# c64-uni-cart-rev5.net
KiCad netlist of a schematic drawn in EAGLE
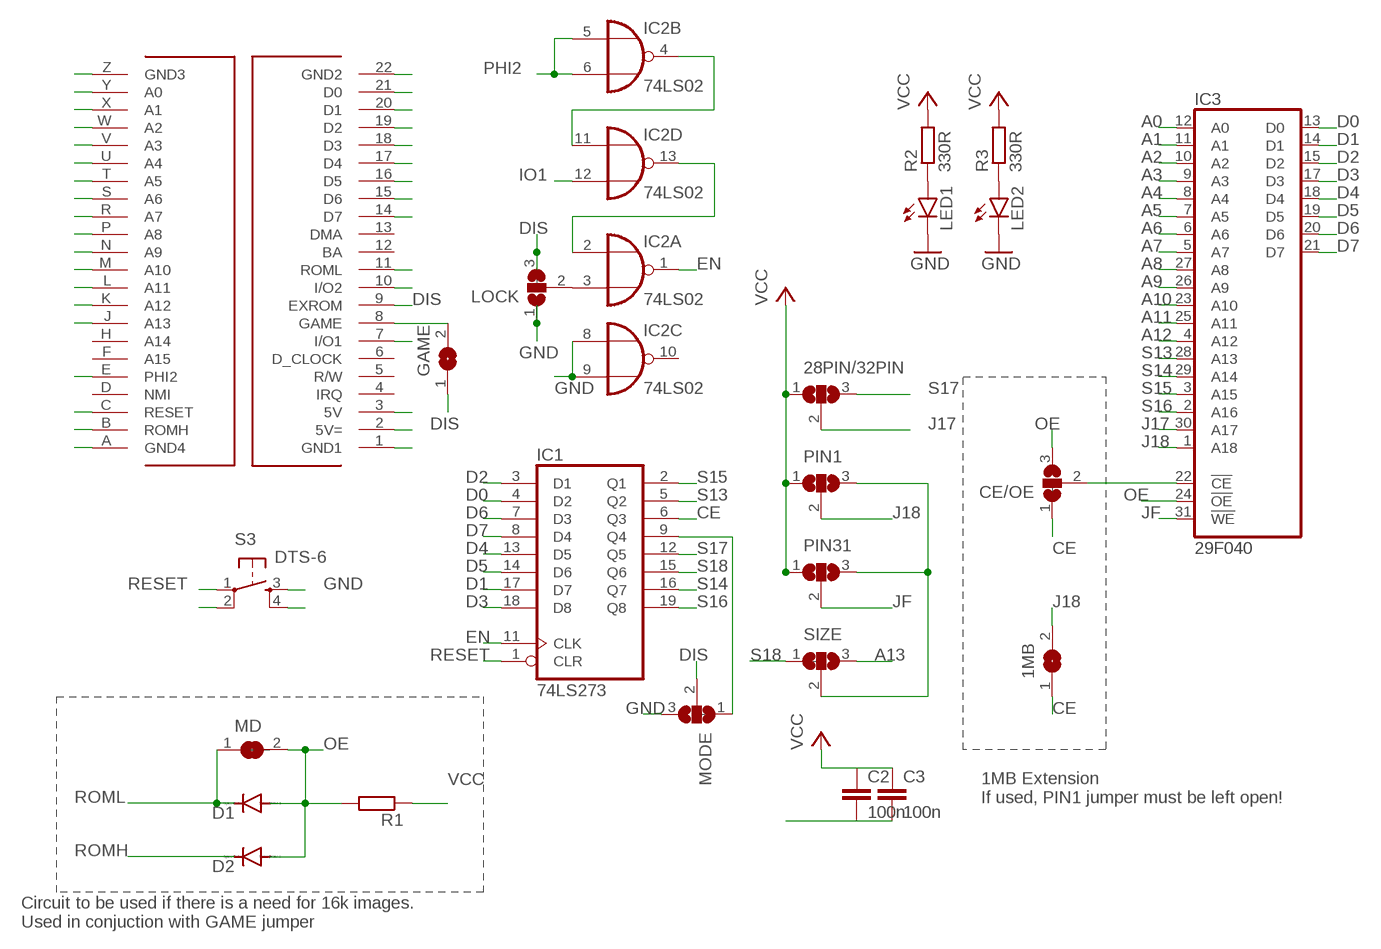
[diagram p0: schematic, sheet 1]

(export (version "E")
  (design (tool "Eeschema 10.0.6"))
  (components
    (comp (ref "1MB") (value "SJ") (footprint "eagle-import:SJ") (libsource (lib "eagle-import") (part "SJ")))
    (comp (ref "28PIN/32PIN")
      (value "SJ2W")
      (footprint "eagle-import:SJ_2")
      (libsource (lib "eagle-import") (part "SJ2W"))
    )
    (comp (ref "C2")
      (value "100n")
      (footprint "eagle-import:C025-024X044")
      (libsource (lib "eagle-import") (part "C-EU025-024X044"))
    )
    (comp (ref "C3")
      (value "100n")
      (footprint "eagle-import:C025-024X044")
      (libsource (lib "eagle-import") (part "C-EU025-024X044"))
    )
    (comp (ref "CE/OE")
      (value "SJ2W")
      (footprint "eagle-import:SJ_2")
      (libsource (lib "eagle-import") (part "SJ2W"))
    )
    (comp (ref "D1")
      (value "DIODE-MINIMELF")
      (footprint "eagle-import:MINIMELF")
      (libsource (lib "eagle-import") (part "DIODE-MINIMELF"))
    )
    (comp (ref "D2")
      (value "DIODE-MINIMELF")
      (footprint "eagle-import:MINIMELF")
      (libsource (lib "eagle-import") (part "DIODE-MINIMELF"))
    )
    (comp (ref "GAME")
      (value "SJ")
      (footprint "eagle-import:SJ")
      (libsource (lib "eagle-import") (part "SJ"))
    )
    (comp (ref "IC1")
      (value "74LS273")
      (footprint "eagle-import:DIL20")
      (libsource (lib "eagle-import") (part "74273NHCT"))
    )
    (comp (ref "IC2")
      (value "74LS02")
      (footprint "eagle-import:DIL14")
      (libsource (lib "eagle-import") (part "7402NLS"))
    )
    (comp (ref "IC3")
      (value "29F040")
      (footprint "eagle-import:DIL32-6")
      (libsource (lib "eagle-import") (part "AM29F040N"))
    )
    (comp (ref "LED1")
      (value "LED3MM")
      (footprint "eagle-import:LED3MM")
      (libsource (lib "eagle-import") (part "LED3MM"))
    )
    (comp (ref "LED2")
      (value "LED3MM")
      (footprint "eagle-import:LED3MM")
      (libsource (lib "eagle-import") (part "LED3MM"))
    )
    (comp (ref "LOCK")
      (value "SJ2W")
      (footprint "eagle-import:SJ_2")
      (libsource (lib "eagle-import") (part "SJ2W"))
    )
    (comp (ref "MD") (value "SJ") (footprint "eagle-import:SJ") (libsource (lib "eagle-import") (part "SJ")))
    (comp (ref "MODE")
      (value "SJ2W")
      (footprint "eagle-import:SJ_2")
      (libsource (lib "eagle-import") (part "SJ2W"))
    )
    (comp (ref "PIN1")
      (value "SJ2W")
      (footprint "eagle-import:SJ_2")
      (libsource (lib "eagle-import") (part "SJ2W"))
    )
    (comp (ref "PIN31")
      (value "SJ2W")
      (footprint "eagle-import:SJ_2")
      (libsource (lib "eagle-import") (part "SJ2W"))
    )
    (comp (ref "R1")
      (value "R-EU_R1206")
      (footprint "eagle-import:R1206")
      (libsource (lib "eagle-import") (part "R-EU_R1206"))
    )
    (comp (ref "R2")
      (value "330R")
      (footprint "eagle-import:R0805")
      (libsource (lib "eagle-import") (part "R-EU_R0805"))
    )
    (comp (ref "R3")
      (value "330R")
      (footprint "eagle-import:R0805")
      (libsource (lib "eagle-import") (part "R-EU_R0805"))
    )
    (comp (ref "S3")
      (value "DTS-6")
      (footprint "eagle-import:DTS-6")
      (libsource (lib "eagle-import") (part "DTS-6"))
    )
    (comp (ref "SIZE")
      (value "SJ2W")
      (footprint "eagle-import:SJ_2")
      (libsource (lib "eagle-import") (part "SJ2W"))
    )
    (comp (ref "U$1")
      (value "C64_CARTRIDGESTUMPY")
      (footprint "eagle-import:C64_STUMPY")
      (libsource (lib "eagle-import") (part "C64_CARTRIDGESTUMPY"))
    )
  )
  (nets
    (net (code "1") (name "/A0") (class "Default")
      (node (ref "IC3") (pin "12") (pinfunction "A0_12") (pintype "input"))
      (node (ref "U$1") (pin "Y") (pinfunction "A0_Y") (pintype "bidirectional"))
    )
    (net (code "2") (name "/A1") (class "Default")
      (node (ref "IC3") (pin "11") (pinfunction "A1_11") (pintype "input"))
      (node (ref "U$1") (pin "X") (pinfunction "A1_X") (pintype "bidirectional"))
    )
    (net (code "3") (name "/A2") (class "Default")
      (node (ref "IC3") (pin "10") (pinfunction "A2_10") (pintype "input"))
      (node (ref "U$1") (pin "W") (pinfunction "A2_W") (pintype "bidirectional"))
    )
    (net (code "4") (name "/A3") (class "Default")
      (node (ref "IC3") (pin "9") (pinfunction "A3_9") (pintype "input"))
      (node (ref "U$1") (pin "V") (pinfunction "A3_V") (pintype "bidirectional"))
    )
    (net (code "5") (name "/A4") (class "Default")
      (node (ref "IC3") (pin "8") (pinfunction "A4_8") (pintype "input"))
      (node (ref "U$1") (pin "U") (pinfunction "A4_U") (pintype "bidirectional"))
    )
    (net (code "6") (name "/A5") (class "Default")
      (node (ref "IC3") (pin "7") (pinfunction "A5_7") (pintype "input"))
      (node (ref "U$1") (pin "T") (pinfunction "A5_T") (pintype "bidirectional"))
    )
    (net (code "7") (name "/A6") (class "Default")
      (node (ref "IC3") (pin "6") (pinfunction "A6_6") (pintype "input"))
      (node (ref "U$1") (pin "S") (pinfunction "A6_S") (pintype "bidirectional"))
    )
    (net (code "8") (name "/A7") (class "Default")
      (node (ref "IC3") (pin "5") (pinfunction "A7_5") (pintype "input"))
      (node (ref "U$1") (pin "R") (pinfunction "A7_R") (pintype "bidirectional"))
    )
    (net (code "9") (name "/A8") (class "Default")
      (node (ref "IC3") (pin "27") (pinfunction "A8_27") (pintype "input"))
      (node (ref "U$1") (pin "P") (pinfunction "A8_P") (pintype "bidirectional"))
    )
    (net (code "10") (name "/A9") (class "Default")
      (node (ref "IC3") (pin "26") (pinfunction "A9_26") (pintype "input"))
      (node (ref "U$1") (pin "N") (pinfunction "A9_N") (pintype "bidirectional"))
    )
    (net (code "11") (name "/A10") (class "Default")
      (node (ref "IC3") (pin "23") (pinfunction "A10_23") (pintype "input"))
      (node (ref "U$1") (pin "M") (pinfunction "A10_M") (pintype "bidirectional"))
    )
    (net (code "12") (name "/A11") (class "Default")
      (node (ref "IC3") (pin "25") (pinfunction "A11_25") (pintype "input"))
      (node (ref "U$1") (pin "L") (pinfunction "A11_L") (pintype "bidirectional"))
    )
    (net (code "13") (name "/A12") (class "Default")
      (node (ref "IC3") (pin "4") (pinfunction "A12_4") (pintype "input"))
      (node (ref "U$1") (pin "K") (pinfunction "A12_K") (pintype "bidirectional"))
    )
    (net (code "14") (name "/A13") (class "Default")
      (node (ref "SIZE") (pin "3") (pinfunction "3_3") (pintype "passive"))
      (node (ref "U$1") (pin "J") (pinfunction "A13_J") (pintype "bidirectional"))
    )
    (net (code "15") (name "/CE") (class "Default")
      (node (ref "1MB") (pin "1") (pinfunction "1_1") (pintype "passive"))
      (node (ref "CE/OE") (pin "1") (pinfunction "1_1") (pintype "passive"))
      (node (ref "IC1") (pin "6") (pinfunction "Q3_6") (pintype "output"))
    )
    (net (code "16") (name "/D0") (class "Default")
      (node (ref "IC1") (pin "4") (pinfunction "D2_4") (pintype "input"))
      (node (ref "IC3") (pin "13") (pinfunction "D0_13") (pintype "tri_state"))
      (node (ref "U$1") (pin "21") (pinfunction "D0_21") (pintype "bidirectional"))
    )
    (net (code "17") (name "/D1") (class "Default")
      (node (ref "IC1") (pin "17") (pinfunction "D7_17") (pintype "input"))
      (node (ref "IC3") (pin "14") (pinfunction "D1_14") (pintype "tri_state"))
      (node (ref "U$1") (pin "20") (pinfunction "D1_20") (pintype "bidirectional"))
    )
    (net (code "18") (name "/D2") (class "Default")
      (node (ref "IC1") (pin "3") (pinfunction "D1_3") (pintype "input"))
      (node (ref "IC3") (pin "15") (pinfunction "D2_15") (pintype "tri_state"))
      (node (ref "U$1") (pin "19") (pinfunction "D2_19") (pintype "bidirectional"))
    )
    (net (code "19") (name "/D3") (class "Default")
      (node (ref "IC1") (pin "18") (pinfunction "D8_18") (pintype "input"))
      (node (ref "IC3") (pin "17") (pinfunction "D3_17") (pintype "tri_state"))
      (node (ref "U$1") (pin "18") (pinfunction "D3_18") (pintype "bidirectional"))
    )
    (net (code "20") (name "/D4") (class "Default")
      (node (ref "IC1") (pin "13") (pinfunction "D5_13") (pintype "input"))
      (node (ref "IC3") (pin "18") (pinfunction "D4_18") (pintype "tri_state"))
      (node (ref "U$1") (pin "17") (pinfunction "D4_17") (pintype "bidirectional"))
    )
    (net (code "21") (name "/D5") (class "Default")
      (node (ref "IC1") (pin "14") (pinfunction "D6_14") (pintype "input"))
      (node (ref "IC3") (pin "19") (pinfunction "D5_19") (pintype "tri_state"))
      (node (ref "U$1") (pin "16") (pinfunction "D5_16") (pintype "bidirectional"))
    )
    (net (code "22") (name "/D6") (class "Default")
      (node (ref "IC1") (pin "7") (pinfunction "D3_7") (pintype "input"))
      (node (ref "IC3") (pin "20") (pinfunction "D6_20") (pintype "tri_state"))
      (node (ref "U$1") (pin "15") (pinfunction "D6_15") (pintype "bidirectional"))
    )
    (net (code "23") (name "/D7") (class "Default")
      (node (ref "IC1") (pin "8") (pinfunction "D4_8") (pintype "input"))
      (node (ref "IC3") (pin "21") (pinfunction "D7_21") (pintype "tri_state"))
      (node (ref "U$1") (pin "14") (pinfunction "D7_14") (pintype "bidirectional"))
    )
    (net (code "24") (name "/DIS") (class "Default")
      (node (ref "GAME") (pin "1") (pinfunction "1_1") (pintype "passive"))
      (node (ref "LOCK") (pin "3") (pinfunction "3_3") (pintype "passive"))
      (node (ref "MODE") (pin "2") (pinfunction "2_2") (pintype "passive"))
      (node (ref "U$1") (pin "9") (pinfunction "EXROM_9") (pintype "bidirectional"))
    )
    (net (code "25") (name "/EN") (class "Default")
      (node (ref "IC1") (pin "11") (pinfunction "CLK_11") (pintype "input"))
      (node (ref "IC2") (pin "1") (pinfunction "O_1") (pintype "output"))
    )
    (net (code "26") (name "/IO1") (class "Default")
      (node (ref "IC2") (pin "12") (pinfunction "I1_12") (pintype "input"))
      (node (ref "U$1") (pin "7") (pinfunction "I/O1_7") (pintype "bidirectional"))
    )
    (net (code "27") (name "/J17") (class "Default")
      (node (ref "28PIN/32PIN") (pin "2") (pinfunction "2_2") (pintype "passive"))
      (node (ref "IC3") (pin "30") (pinfunction "A17_30") (pintype "input"))
    )
    (net (code "28") (name "/J18") (class "Default")
      (node (ref "1MB") (pin "2") (pinfunction "2_2") (pintype "passive"))
      (node (ref "IC3") (pin "1") (pinfunction "A18_1") (pintype "input"))
      (node (ref "PIN1") (pin "2") (pinfunction "2_2") (pintype "passive"))
    )
    (net (code "29") (name "/JF") (class "Default")
      (node (ref "IC3") (pin "31") (pinfunction "~{WE}_31") (pintype "input"))
      (node (ref "PIN31") (pin "2") (pinfunction "2_2") (pintype "passive"))
    )
    (net (code "30") (name "/OE") (class "Default")
      (node (ref "CE/OE") (pin "3") (pinfunction "3_3") (pintype "passive"))
      (node (ref "D1") (pin "A") (pinfunction "A_A") (pintype "passive"))
      (node (ref "D2") (pin "A") (pinfunction "A_A") (pintype "passive"))
      (node (ref "IC3") (pin "24") (pinfunction "~{OE}_24") (pintype "input"))
      (node (ref "MD") (pin "2") (pinfunction "2_2") (pintype "passive"))
      (node (ref "R1") (pin "2") (pinfunction "2_2") (pintype "passive"))
    )
    (net (code "31") (name "/PHI2") (class "Default")
      (node (ref "IC2") (pin "5") (pinfunction "I0_5") (pintype "input"))
      (node (ref "IC2") (pin "6") (pinfunction "I1_6") (pintype "input"))
      (node (ref "U$1") (pin "E") (pinfunction "PHI2_E") (pintype "bidirectional"))
    )
    (net (code "32") (name "/RESET") (class "Default")
      (node (ref "IC1") (pin "1") (pinfunction "CLR_1") (pintype "input"))
      (node (ref "S3") (pin "1") (pinfunction "1_1") (pintype "passive"))
      (node (ref "S3") (pin "2") (pinfunction "2_2") (pintype "passive"))
      (node (ref "U$1") (pin "C") (pinfunction "RESET_C") (pintype "bidirectional"))
    )
    (net (code "33") (name "/ROMH") (class "Default")
      (node (ref "D2") (pin "C") (pinfunction "C_C") (pintype "passive"))
      (node (ref "U$1") (pin "B") (pinfunction "ROMH_B") (pintype "bidirectional"))
    )
    (net (code "34") (name "/ROML") (class "Default")
      (node (ref "D1") (pin "C") (pinfunction "C_C") (pintype "passive"))
      (node (ref "MD") (pin "1") (pinfunction "1_1") (pintype "passive"))
      (node (ref "U$1") (pin "11") (pinfunction "ROML_11") (pintype "bidirectional"))
    )
    (net (code "35") (name "/S13") (class "Default")
      (node (ref "IC1") (pin "5") (pinfunction "Q2_5") (pintype "output"))
      (node (ref "IC3") (pin "28") (pinfunction "A13_28") (pintype "input"))
    )
    (net (code "36") (name "/S14") (class "Default")
      (node (ref "IC1") (pin "16") (pinfunction "Q7_16") (pintype "output"))
      (node (ref "IC3") (pin "29") (pinfunction "A14_29") (pintype "input"))
    )
    (net (code "37") (name "/S15") (class "Default")
      (node (ref "IC1") (pin "2") (pinfunction "Q1_2") (pintype "output"))
      (node (ref "IC3") (pin "3") (pinfunction "A15_3") (pintype "input"))
    )
    (net (code "38") (name "/S16") (class "Default")
      (node (ref "IC1") (pin "19") (pinfunction "Q8_19") (pintype "output"))
      (node (ref "IC3") (pin "2") (pinfunction "A16_2") (pintype "input"))
    )
    (net (code "39") (name "/S17") (class "Default")
      (node (ref "28PIN/32PIN") (pin "3") (pinfunction "3_3") (pintype "passive"))
      (node (ref "IC1") (pin "12") (pinfunction "Q5_12") (pintype "output"))
    )
    (net (code "40") (name "/S18") (class "Default")
      (node (ref "IC1") (pin "15") (pinfunction "Q6_15") (pintype "output"))
      (node (ref "SIZE") (pin "1") (pinfunction "1_1") (pintype "passive"))
    )
    (net (code "41") (name "GND") (class "Default")
      (node (ref "C2") (pin "2") (pinfunction "2_2") (pintype "passive"))
      (node (ref "C3") (pin "2") (pinfunction "2_2") (pintype "passive"))
      (node (ref "IC2") (pin "8") (pinfunction "I0_8") (pintype "input"))
      (node (ref "IC2") (pin "9") (pinfunction "I1_9") (pintype "input"))
      (node (ref "LED1") (pin "K") (pinfunction "C_K") (pintype "passive"))
      (node (ref "LED2") (pin "K") (pinfunction "C_K") (pintype "passive"))
      (node (ref "LOCK") (pin "1") (pinfunction "1_1") (pintype "passive"))
      (node (ref "MODE") (pin "3") (pinfunction "3_3") (pintype "passive"))
      (node (ref "S3") (pin "3") (pinfunction "3_3") (pintype "passive"))
      (node (ref "S3") (pin "4") (pinfunction "4_4") (pintype "passive"))
      (node (ref "U$1") (pin "1") (pinfunction "GND1_1") (pintype "bidirectional"))
      (node (ref "U$1") (pin "22") (pinfunction "GND2_22") (pintype "bidirectional"))
      (node (ref "U$1") (pin "A") (pinfunction "GND4_A") (pintype "bidirectional"))
      (node (ref "U$1") (pin "Z") (pinfunction "GND3_Z") (pintype "bidirectional"))
    )
    (net (code "42") (name "Net-(IC1A-Q4)") (class "Default")
      (node (ref "IC1") (pin "9") (pinfunction "Q4_9") (pintype "output"))
      (node (ref "MODE") (pin "1") (pinfunction "1_1") (pintype "passive"))
    )
    (net (code "43") (name "Net-(IC2A-I0)") (class "Default")
      (node (ref "IC2") (pin "13") (pinfunction "O_13") (pintype "output"))
      (node (ref "IC2") (pin "2") (pinfunction "I0_2") (pintype "input"))
    )
    (net (code "44") (name "Net-(IC2A-I1)") (class "Default")
      (node (ref "IC2") (pin "3") (pinfunction "I1_3") (pintype "input"))
      (node (ref "LOCK") (pin "2") (pinfunction "2_2") (pintype "passive"))
    )
    (net (code "45") (name "Net-(IC2B-O)") (class "Default")
      (node (ref "IC2") (pin "11") (pinfunction "I0_11") (pintype "input"))
      (node (ref "IC2") (pin "4") (pinfunction "O_4") (pintype "output"))
    )
    (net (code "46") (name "Net-(IC3A-~{CE})") (class "Default")
      (node (ref "CE/OE") (pin "2") (pinfunction "2_2") (pintype "passive"))
      (node (ref "IC3") (pin "22") (pinfunction "~{CE}_22") (pintype "input"))
    )
    (net (code "47") (name "Net-(LED1-PadA)") (class "Default")
      (node (ref "LED1") (pin "A") (pinfunction "A_A") (pintype "passive"))
      (node (ref "R2") (pin "1") (pinfunction "1_1") (pintype "passive"))
    )
    (net (code "48") (name "Net-(LED2-PadA)") (class "Default")
      (node (ref "LED2") (pin "A") (pinfunction "A_A") (pintype "passive"))
      (node (ref "R3") (pin "1") (pinfunction "1_1") (pintype "passive"))
    )
    (net (code "49") (name "Net-(PIN1-Pad3)") (class "Default")
      (node (ref "PIN1") (pin "3") (pinfunction "3_3") (pintype "passive"))
      (node (ref "PIN31") (pin "3") (pinfunction "3_3") (pintype "passive"))
      (node (ref "SIZE") (pin "2") (pinfunction "2_2") (pintype "passive"))
    )
    (net (code "50") (name "Net-(U$1-GAME)") (class "Default")
      (node (ref "GAME") (pin "2") (pinfunction "2_2") (pintype "passive"))
      (node (ref "U$1") (pin "8") (pinfunction "GAME_8") (pintype "bidirectional"))
    )
    (net (code "51") (name "VCC") (class "Default")
      (node (ref "28PIN/32PIN") (pin "1") (pinfunction "1_1") (pintype "passive"))
      (node (ref "C2") (pin "1") (pinfunction "1_1") (pintype "passive"))
      (node (ref "C3") (pin "1") (pinfunction "1_1") (pintype "passive"))
      (node (ref "PIN1") (pin "1") (pinfunction "1_1") (pintype "passive"))
      (node (ref "PIN31") (pin "1") (pinfunction "1_1") (pintype "passive"))
      (node (ref "R1") (pin "1") (pinfunction "1_1") (pintype "passive"))
      (node (ref "R2") (pin "2") (pinfunction "2_2") (pintype "passive"))
      (node (ref "R3") (pin "2") (pinfunction "2_2") (pintype "passive"))
      (node (ref "U$1") (pin "2") (pinfunction "5V=_2") (pintype "bidirectional"))
      (node (ref "U$1") (pin "3") (pinfunction "5V_3") (pintype "bidirectional"))
    )
    (net (code "52") (name "unconnected-(IC2C-O-Pad10)") (class "Default")
      (node (ref "IC2") (pin "10") (pinfunction "O_10") (pintype "output"))
    )
    (net (code "53") (name "unconnected-(U$1-A14-PadH)") (class "Default")
      (node (ref "U$1") (pin "H") (pinfunction "A14_H") (pintype "bidirectional"))
    )
    (net (code "54") (name "unconnected-(U$1-A15-PadF)") (class "Default")
      (node (ref "U$1") (pin "F") (pinfunction "A15_F") (pintype "bidirectional"))
    )
    (net (code "55") (name "unconnected-(U$1-BA-Pad12)") (class "Default")
      (node (ref "U$1") (pin "12") (pinfunction "BA_12") (pintype "bidirectional"))
    )
    (net (code "56") (name "unconnected-(U$1-DMA-Pad13)") (class "Default")
      (node (ref "U$1") (pin "13") (pinfunction "DMA_13") (pintype "bidirectional"))
    )
    (net (code "57") (name "unconnected-(U$1-D_CLOCK-Pad6)") (class "Default")
      (node (ref "U$1") (pin "6") (pinfunction "D_CLOCK_6") (pintype "bidirectional"))
    )
    (net (code "58") (name "unconnected-(U$1-IRQ-Pad4)") (class "Default")
      (node (ref "U$1") (pin "4") (pinfunction "IRQ_4") (pintype "bidirectional"))
    )
    (net (code "59") (name "unconnected-(U$1-I{slash}O2-Pad10)") (class "Default")
      (node (ref "U$1") (pin "10") (pinfunction "I/O2_10") (pintype "bidirectional"))
    )
    (net (code "60") (name "unconnected-(U$1-NMI-PadD)") (class "Default")
      (node (ref "U$1") (pin "D") (pinfunction "NMI_D") (pintype "bidirectional"))
    )
    (net (code "61") (name "unconnected-(U$1-R{slash}W-Pad5)") (class "Default")
      (node (ref "U$1") (pin "5") (pinfunction "R/W_5") (pintype "bidirectional"))
    )
  )
)
